# alimrobotmobile.net
KiCad netlist of a schematic drawn in EAGLE
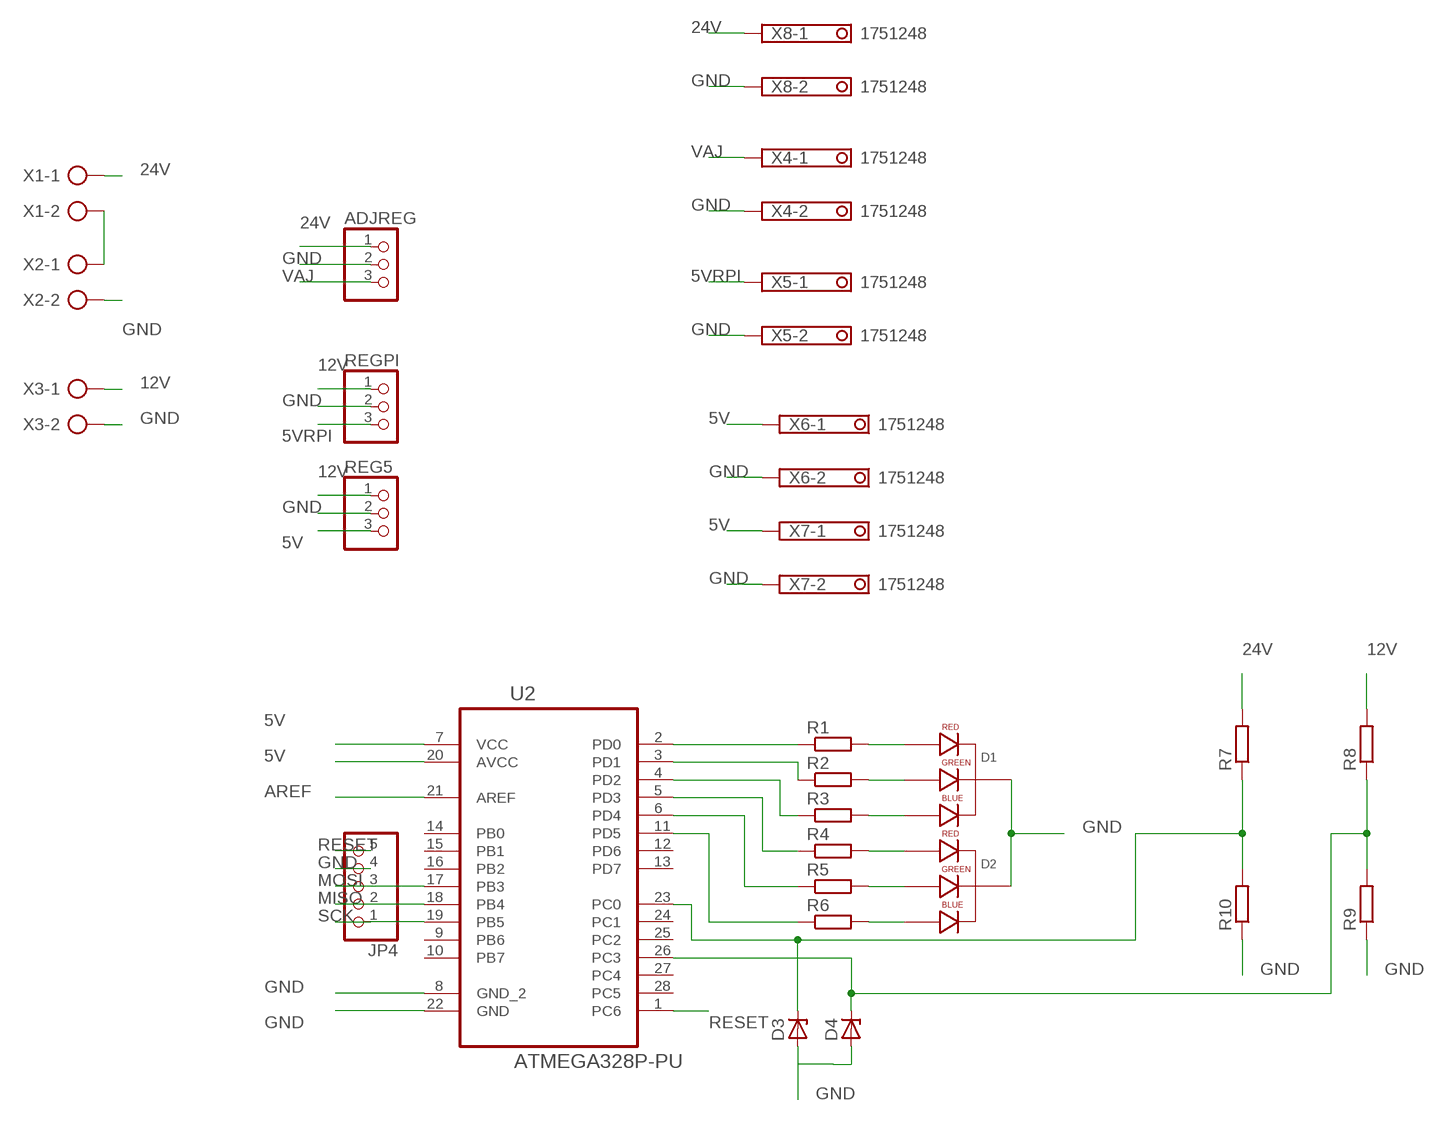
[diagram p0: schematic, sheet 1]

(export (version "E")
  (design (tool "Eeschema 10.0.6"))
  (components
    (comp (ref "ADJREG")
      (value "PINHD-1X3")
      (footprint "eagle-import:1X03")
      (libsource (lib "eagle-import") (part "PINHD-1X3"))
    )
    (comp (ref "D1")
      (value "LED-RGB-CC-THRUCLEAR")
      (footprint "eagle-import:LED-RGB-THRU")
      (libsource (lib "eagle-import") (part "LED-RGB-CC-THRUCLEAR"))
    )
    (comp (ref "D2")
      (value "LED-RGB-CC-THRUCLEAR")
      (footprint "eagle-import:LED-RGB-THRU")
      (libsource (lib "eagle-import") (part "LED-RGB-CC-THRUCLEAR"))
    )
    (comp (ref "D3")
      (value "ZENER-DIODEZD-12.5")
      (footprint "eagle-import:ZDIO12.5")
      (libsource (lib "eagle-import") (part "ZENER-DIODEZD-12.5"))
    )
    (comp (ref "D4")
      (value "ZENER-DIODEZD-12.5")
      (footprint "eagle-import:ZDIO12.5")
      (libsource (lib "eagle-import") (part "ZENER-DIODEZD-12.5"))
    )
    (comp (ref "JP4")
      (value "PINHD-1X5")
      (footprint "eagle-import:1X05")
      (libsource (lib "eagle-import") (part "PINHD-1X5"))
    )
    (comp (ref "R1")
      (value "R-EU_0207/12")
      (footprint "eagle-import:0207_12")
      (libsource (lib "eagle-import") (part "R-EU_0207/12"))
    )
    (comp (ref "R2")
      (value "R-EU_0207/12")
      (footprint "eagle-import:0207_12")
      (libsource (lib "eagle-import") (part "R-EU_0207/12"))
    )
    (comp (ref "R3")
      (value "R-EU_0207/12")
      (footprint "eagle-import:0207_12")
      (libsource (lib "eagle-import") (part "R-EU_0207/12"))
    )
    (comp (ref "R4")
      (value "R-EU_0207/12")
      (footprint "eagle-import:0207_12")
      (libsource (lib "eagle-import") (part "R-EU_0207/12"))
    )
    (comp (ref "R5")
      (value "R-EU_0207/12")
      (footprint "eagle-import:0207_12")
      (libsource (lib "eagle-import") (part "R-EU_0207/12"))
    )
    (comp (ref "R6")
      (value "R-EU_0207/12")
      (footprint "eagle-import:0207_12")
      (libsource (lib "eagle-import") (part "R-EU_0207/12"))
    )
    (comp (ref "R7")
      (value "R-EU_0207/12")
      (footprint "eagle-import:0207_12")
      (libsource (lib "eagle-import") (part "R-EU_0207/12"))
    )
    (comp (ref "R8")
      (value "R-EU_0207/12")
      (footprint "eagle-import:0207_12")
      (libsource (lib "eagle-import") (part "R-EU_0207/12"))
    )
    (comp (ref "R9")
      (value "R-EU_0207/12")
      (footprint "eagle-import:0207_12")
      (libsource (lib "eagle-import") (part "R-EU_0207/12"))
    )
    (comp (ref "R10")
      (value "R-EU_0207/12")
      (footprint "eagle-import:0207_12")
      (libsource (lib "eagle-import") (part "R-EU_0207/12"))
    )
    (comp (ref "REG5")
      (value "PINHD-1X3")
      (footprint "eagle-import:1X03")
      (libsource (lib "eagle-import") (part "PINHD-1X3"))
    )
    (comp (ref "REGPI")
      (value "PINHD-1X3")
      (footprint "eagle-import:1X03")
      (libsource (lib "eagle-import") (part "PINHD-1X3"))
    )
    (comp (ref "U2")
      (value "ATMEGA328P-PU")
      (footprint "eagle-import:DIP254P762X457-28")
      (libsource (lib "eagle-import") (part "ATMEGA328P-PU"))
    )
    (comp (ref "X1")
      (value "AK300/2")
      (footprint "eagle-import:AK300_2")
      (libsource (lib "eagle-import") (part "AK300/2"))
    )
    (comp (ref "X2")
      (value "AK300/2")
      (footprint "eagle-import:AK300_2")
      (libsource (lib "eagle-import") (part "AK300/2"))
    )
    (comp (ref "X3")
      (value "AK300/2")
      (footprint "eagle-import:AK300_2")
      (libsource (lib "eagle-import") (part "AK300/2"))
    )
    (comp (ref "X4")
      (value "1751248")
      (footprint "eagle-import:1751248")
      (libsource (lib "eagle-import") (part "1751248"))
    )
    (comp (ref "X5")
      (value "1751248")
      (footprint "eagle-import:1751248")
      (libsource (lib "eagle-import") (part "1751248"))
    )
    (comp (ref "X6")
      (value "1751248")
      (footprint "eagle-import:1751248")
      (libsource (lib "eagle-import") (part "1751248"))
    )
    (comp (ref "X7")
      (value "1751248")
      (footprint "eagle-import:1751248")
      (libsource (lib "eagle-import") (part "1751248"))
    )
    (comp (ref "X8")
      (value "1751248")
      (footprint "eagle-import:1751248")
      (libsource (lib "eagle-import") (part "1751248"))
    )
  )
  (nets
    (net (code "1") (name "/5V") (class "Default")
      (node (ref "REG5") (pin "3") (pinfunction "3_3") (pintype "passive"))
      (node (ref "U2") (pin "20") (pinfunction "AVCC_20") (pintype "power_in"))
      (node (ref "U2") (pin "7") (pinfunction "VCC_7") (pintype "power_in"))
      (node (ref "X6") (pin "1") (pinfunction "K_1") (pintype "passive"))
      (node (ref "X7") (pin "1") (pinfunction "K_1") (pintype "passive"))
    )
    (net (code "2") (name "/5VRPI") (class "Default")
      (node (ref "REGPI") (pin "3") (pinfunction "3_3") (pintype "passive"))
      (node (ref "X5") (pin "1") (pinfunction "K_1") (pintype "passive"))
    )
    (net (code "3") (name "/12V") (class "Default")
      (node (ref "R8") (pin "2") (pinfunction "2_2") (pintype "passive"))
      (node (ref "REG5") (pin "1") (pinfunction "1_1") (pintype "passive"))
      (node (ref "REGPI") (pin "1") (pinfunction "1_1") (pintype "passive"))
      (node (ref "X3") (pin "1") (pinfunction "KL_1") (pintype "passive"))
    )
    (net (code "4") (name "/24V") (class "Default")
      (node (ref "ADJREG") (pin "1") (pinfunction "1_1") (pintype "passive"))
      (node (ref "R7") (pin "2") (pinfunction "2_2") (pintype "passive"))
      (node (ref "X1") (pin "1") (pinfunction "KL_1") (pintype "passive"))
      (node (ref "X8") (pin "1") (pinfunction "K_1") (pintype "passive"))
    )
    (net (code "5") (name "/AREF") (class "Default")
      (node (ref "U2") (pin "21") (pinfunction "AREF_21") (pintype "input"))
    )
    (net (code "6") (name "/GND") (class "Default")
      (node (ref "ADJREG") (pin "2") (pinfunction "2_2") (pintype "passive"))
      (node (ref "D1") (pin "2") (pinfunction "CATHODE_2") (pintype "bidirectional"))
      (node (ref "D2") (pin "2") (pinfunction "CATHODE_2") (pintype "bidirectional"))
      (node (ref "D3") (pin "A") (pinfunction "A_A") (pintype "passive"))
      (node (ref "D4") (pin "A") (pinfunction "A_A") (pintype "passive"))
      (node (ref "JP4") (pin "4") (pinfunction "4_4") (pintype "passive"))
      (node (ref "R10") (pin "1") (pinfunction "1_1") (pintype "passive"))
      (node (ref "R9") (pin "1") (pinfunction "1_1") (pintype "passive"))
      (node (ref "REG5") (pin "2") (pinfunction "2_2") (pintype "passive"))
      (node (ref "REGPI") (pin "2") (pinfunction "2_2") (pintype "passive"))
      (node (ref "U2") (pin "22") (pinfunction "GND_22") (pintype "passive"))
      (node (ref "U2") (pin "8") (pinfunction "GND_2_8") (pintype "passive"))
      (node (ref "X2") (pin "2") (pinfunction "KL_2") (pintype "passive"))
      (node (ref "X3") (pin "2") (pinfunction "KL_2") (pintype "passive"))
      (node (ref "X4") (pin "2") (pinfunction "K_2") (pintype "passive"))
      (node (ref "X5") (pin "2") (pinfunction "K_2") (pintype "passive"))
      (node (ref "X6") (pin "2") (pinfunction "K_2") (pintype "passive"))
      (node (ref "X7") (pin "2") (pinfunction "K_2") (pintype "passive"))
      (node (ref "X8") (pin "2") (pinfunction "K_2") (pintype "passive"))
    )
    (net (code "7") (name "/MISO") (class "Default")
      (node (ref "JP4") (pin "2") (pinfunction "2_2") (pintype "passive"))
      (node (ref "U2") (pin "18") (pinfunction "PB4_18") (pintype "bidirectional"))
    )
    (net (code "8") (name "/MOSI") (class "Default")
      (node (ref "JP4") (pin "3") (pinfunction "3_3") (pintype "passive"))
      (node (ref "U2") (pin "17") (pinfunction "PB3_17") (pintype "bidirectional"))
    )
    (net (code "9") (name "/RESET") (class "Default")
      (node (ref "JP4") (pin "5") (pinfunction "5_5") (pintype "passive"))
      (node (ref "U2") (pin "1") (pinfunction "PC6_1") (pintype "bidirectional"))
    )
    (net (code "10") (name "/SCK") (class "Default")
      (node (ref "JP4") (pin "1") (pinfunction "1_1") (pintype "passive"))
      (node (ref "U2") (pin "19") (pinfunction "PB5_19") (pintype "bidirectional"))
    )
    (net (code "11") (name "/VAJ") (class "Default")
      (node (ref "ADJREG") (pin "3") (pinfunction "3_3") (pintype "passive"))
      (node (ref "X4") (pin "1") (pinfunction "K_1") (pintype "passive"))
    )
    (net (code "12") (name "Net-(D1-BLUE_CATHODE)") (class "Default")
      (node (ref "D1") (pin "4") (pinfunction "BLUE_CATHODE_4") (pintype "bidirectional"))
      (node (ref "R3") (pin "2") (pinfunction "2_2") (pintype "passive"))
    )
    (net (code "13") (name "Net-(D1-GREEN_CATHODE)") (class "Default")
      (node (ref "D1") (pin "3") (pinfunction "GREEN_CATHODE_3") (pintype "bidirectional"))
      (node (ref "R2") (pin "2") (pinfunction "2_2") (pintype "passive"))
    )
    (net (code "14") (name "Net-(D1-RED_CATHODE)") (class "Default")
      (node (ref "D1") (pin "1") (pinfunction "RED_CATHODE_1") (pintype "bidirectional"))
      (node (ref "R1") (pin "2") (pinfunction "2_2") (pintype "passive"))
    )
    (net (code "15") (name "Net-(D2-BLUE_CATHODE)") (class "Default")
      (node (ref "D2") (pin "4") (pinfunction "BLUE_CATHODE_4") (pintype "bidirectional"))
      (node (ref "R6") (pin "2") (pinfunction "2_2") (pintype "passive"))
    )
    (net (code "16") (name "Net-(D2-GREEN_CATHODE)") (class "Default")
      (node (ref "D2") (pin "3") (pinfunction "GREEN_CATHODE_3") (pintype "bidirectional"))
      (node (ref "R5") (pin "2") (pinfunction "2_2") (pintype "passive"))
    )
    (net (code "17") (name "Net-(D2-RED_CATHODE)") (class "Default")
      (node (ref "D2") (pin "1") (pinfunction "RED_CATHODE_1") (pintype "bidirectional"))
      (node (ref "R4") (pin "2") (pinfunction "2_2") (pintype "passive"))
    )
    (net (code "18") (name "Net-(U2-PC0)") (class "Default")
      (node (ref "D3") (pin "C") (pinfunction "C_C") (pintype "passive"))
      (node (ref "R10") (pin "2") (pinfunction "2_2") (pintype "passive"))
      (node (ref "R7") (pin "1") (pinfunction "1_1") (pintype "passive"))
      (node (ref "U2") (pin "23") (pinfunction "PC0_23") (pintype "bidirectional"))
    )
    (net (code "19") (name "Net-(U2-PC3)") (class "Default")
      (node (ref "D4") (pin "C") (pinfunction "C_C") (pintype "passive"))
      (node (ref "R8") (pin "1") (pinfunction "1_1") (pintype "passive"))
      (node (ref "R9") (pin "2") (pinfunction "2_2") (pintype "passive"))
      (node (ref "U2") (pin "26") (pinfunction "PC3_26") (pintype "bidirectional"))
    )
    (net (code "20") (name "Net-(U2-PD0)") (class "Default")
      (node (ref "R1") (pin "1") (pinfunction "1_1") (pintype "passive"))
      (node (ref "U2") (pin "2") (pinfunction "PD0_2") (pintype "bidirectional"))
    )
    (net (code "21") (name "Net-(U2-PD1)") (class "Default")
      (node (ref "R2") (pin "1") (pinfunction "1_1") (pintype "passive"))
      (node (ref "U2") (pin "3") (pinfunction "PD1_3") (pintype "bidirectional"))
    )
    (net (code "22") (name "Net-(U2-PD2)") (class "Default")
      (node (ref "R3") (pin "1") (pinfunction "1_1") (pintype "passive"))
      (node (ref "U2") (pin "4") (pinfunction "PD2_4") (pintype "bidirectional"))
    )
    (net (code "23") (name "Net-(U2-PD3)") (class "Default")
      (node (ref "R4") (pin "1") (pinfunction "1_1") (pintype "passive"))
      (node (ref "U2") (pin "5") (pinfunction "PD3_5") (pintype "bidirectional"))
    )
    (net (code "24") (name "Net-(U2-PD4)") (class "Default")
      (node (ref "R5") (pin "1") (pinfunction "1_1") (pintype "passive"))
      (node (ref "U2") (pin "6") (pinfunction "PD4_6") (pintype "bidirectional"))
    )
    (net (code "25") (name "Net-(U2-PD5)") (class "Default")
      (node (ref "R6") (pin "1") (pinfunction "1_1") (pintype "passive"))
      (node (ref "U2") (pin "11") (pinfunction "PD5_11") (pintype "bidirectional"))
    )
    (net (code "26") (name "Net-(X1B-KL)") (class "Default")
      (node (ref "X1") (pin "2") (pinfunction "KL_2") (pintype "passive"))
      (node (ref "X2") (pin "1") (pinfunction "KL_1") (pintype "passive"))
    )
    (net (code "27") (name "unconnected-(U2-PB0-Pad14)") (class "Default")
      (node (ref "U2") (pin "14") (pinfunction "PB0_14") (pintype "bidirectional"))
    )
    (net (code "28") (name "unconnected-(U2-PB1-Pad15)") (class "Default")
      (node (ref "U2") (pin "15") (pinfunction "PB1_15") (pintype "bidirectional"))
    )
    (net (code "29") (name "unconnected-(U2-PB2-Pad16)") (class "Default")
      (node (ref "U2") (pin "16") (pinfunction "PB2_16") (pintype "bidirectional"))
    )
    (net (code "30") (name "unconnected-(U2-PB6-Pad9)") (class "Default")
      (node (ref "U2") (pin "9") (pinfunction "PB6_9") (pintype "bidirectional"))
    )
    (net (code "31") (name "unconnected-(U2-PB7-Pad10)") (class "Default")
      (node (ref "U2") (pin "10") (pinfunction "PB7_10") (pintype "bidirectional"))
    )
    (net (code "32") (name "unconnected-(U2-PC1-Pad24)") (class "Default")
      (node (ref "U2") (pin "24") (pinfunction "PC1_24") (pintype "bidirectional"))
    )
    (net (code "33") (name "unconnected-(U2-PC2-Pad25)") (class "Default")
      (node (ref "U2") (pin "25") (pinfunction "PC2_25") (pintype "bidirectional"))
    )
    (net (code "34") (name "unconnected-(U2-PC4-Pad27)") (class "Default")
      (node (ref "U2") (pin "27") (pinfunction "PC4_27") (pintype "bidirectional"))
    )
    (net (code "35") (name "unconnected-(U2-PC5-Pad28)") (class "Default")
      (node (ref "U2") (pin "28") (pinfunction "PC5_28") (pintype "bidirectional"))
    )
    (net (code "36") (name "unconnected-(U2-PD6-Pad12)") (class "Default")
      (node (ref "U2") (pin "12") (pinfunction "PD6_12") (pintype "bidirectional"))
    )
    (net (code "37") (name "unconnected-(U2-PD7-Pad13)") (class "Default")
      (node (ref "U2") (pin "13") (pinfunction "PD7_13") (pintype "bidirectional"))
    )
  )
)
